# ADLX362.net
KiCad netlist of a schematic drawn in Altium Designer
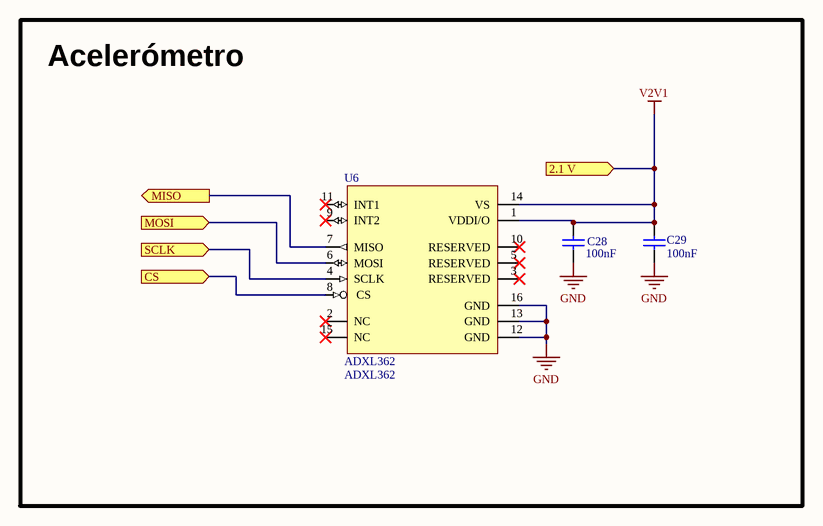
[diagram p0: ADLX362.SchDoc]

(export (version "E")
  (design (tool "Eeschema 10.0.6"))
  (components
    (comp (ref "C28")
      (value "100nF")
      (footprint "CAPC1005X55X25ML05T10")
      (fields (field (name "MANUFACTURER") "Murata") (field (name "PART NUMBER") "GRM1555C1H1R2BA01D"))
      (libsource (lib "Altium Content Vault") (part "CAP"))
    )
    (comp (ref "C29")
      (value "100nF")
      (footprint "CAPC1005X55X25ML05T10")
      (fields (field (name "MANUFACTURER") "Murata") (field (name "PART NUMBER") "GRM1555C1H1R2BA01D"))
      (libsource (lib "Altium Content Vault") (part "CAP"))
    )
    (comp (ref "U6")
      (value "ADXL362")
      (footprint "ADXL362 - duplicate")
      (libsource (lib "DEOP2021") (part "ADXL362"))
    )
  )
  (nets
    (net (code "1") (name "/CS") (class "Default")
      (node (ref "U6") (pin "8") (pinfunction "CS_8") (pintype "input"))
    )
    (net (code "2") (name "/MISO") (class "Default")
      (node (ref "U6") (pin "7") (pinfunction "MISO_7") (pintype "output"))
    )
    (net (code "3") (name "/MOSI") (class "Default")
      (node (ref "U6") (pin "6") (pinfunction "MOSI_6") (pintype "bidirectional"))
    )
    (net (code "4") (name "/SCLK") (class "Default")
      (node (ref "U6") (pin "4") (pinfunction "SCLK_4") (pintype "input"))
    )
    (net (code "5") (name "GND") (class "Default")
      (node (ref "C28") (pin "1") (pinfunction "1_1") (pintype "passive"))
      (node (ref "C29") (pin "1") (pinfunction "1_1") (pintype "passive"))
      (node (ref "U6") (pin "12") (pinfunction "GND_12") (pintype "power_in"))
      (node (ref "U6") (pin "13") (pinfunction "GND_13") (pintype "power_in"))
      (node (ref "U6") (pin "16") (pinfunction "GND_16") (pintype "power_in"))
    )
    (net (code "6") (name "V2V1") (class "Default")
      (node (ref "C28") (pin "2") (pinfunction "2_2") (pintype "passive"))
      (node (ref "C29") (pin "2") (pinfunction "2_2") (pintype "passive"))
      (node (ref "U6") (pin "1") (pinfunction "VDDI/O_1") (pintype "power_in"))
      (node (ref "U6") (pin "14") (pinfunction "VS_14") (pintype "power_in"))
    )
    (net (code "7") (name "unconnected-(U6-INT1-Pad11)") (class "Default")
      (node (ref "U6") (pin "11") (pinfunction "INT1_11") (pintype "bidirectional+no_connect"))
    )
    (net (code "8") (name "unconnected-(U6-INT2-Pad9)") (class "Default")
      (node (ref "U6") (pin "9") (pinfunction "INT2_9") (pintype "bidirectional+no_connect"))
    )
    (net (code "9") (name "unconnected-(U6-NC-Pad2)") (class "Default")
      (node (ref "U6") (pin "2") (pinfunction "NC_2") (pintype "passive+no_connect"))
    )
    (net (code "10") (name "unconnected-(U6-NC-Pad15)") (class "Default")
      (node (ref "U6") (pin "15") (pinfunction "NC_15") (pintype "passive+no_connect"))
    )
    (net (code "11") (name "unconnected-(U6-RESERVED-Pad3)") (class "Default")
      (node (ref "U6") (pin "3") (pinfunction "RESERVED_3") (pintype "passive+no_connect"))
    )
    (net (code "12") (name "unconnected-(U6-RESERVED-Pad5)") (class "Default")
      (node (ref "U6") (pin "5") (pinfunction "RESERVED_5") (pintype "passive+no_connect"))
    )
    (net (code "13") (name "unconnected-(U6-RESERVED-Pad10)") (class "Default")
      (node (ref "U6") (pin "10") (pinfunction "RESERVED_10") (pintype "passive+no_connect"))
    )
  )
)
